# eib-32-intan-hs.net
KiCad netlist of a schematic drawn in EAGLE
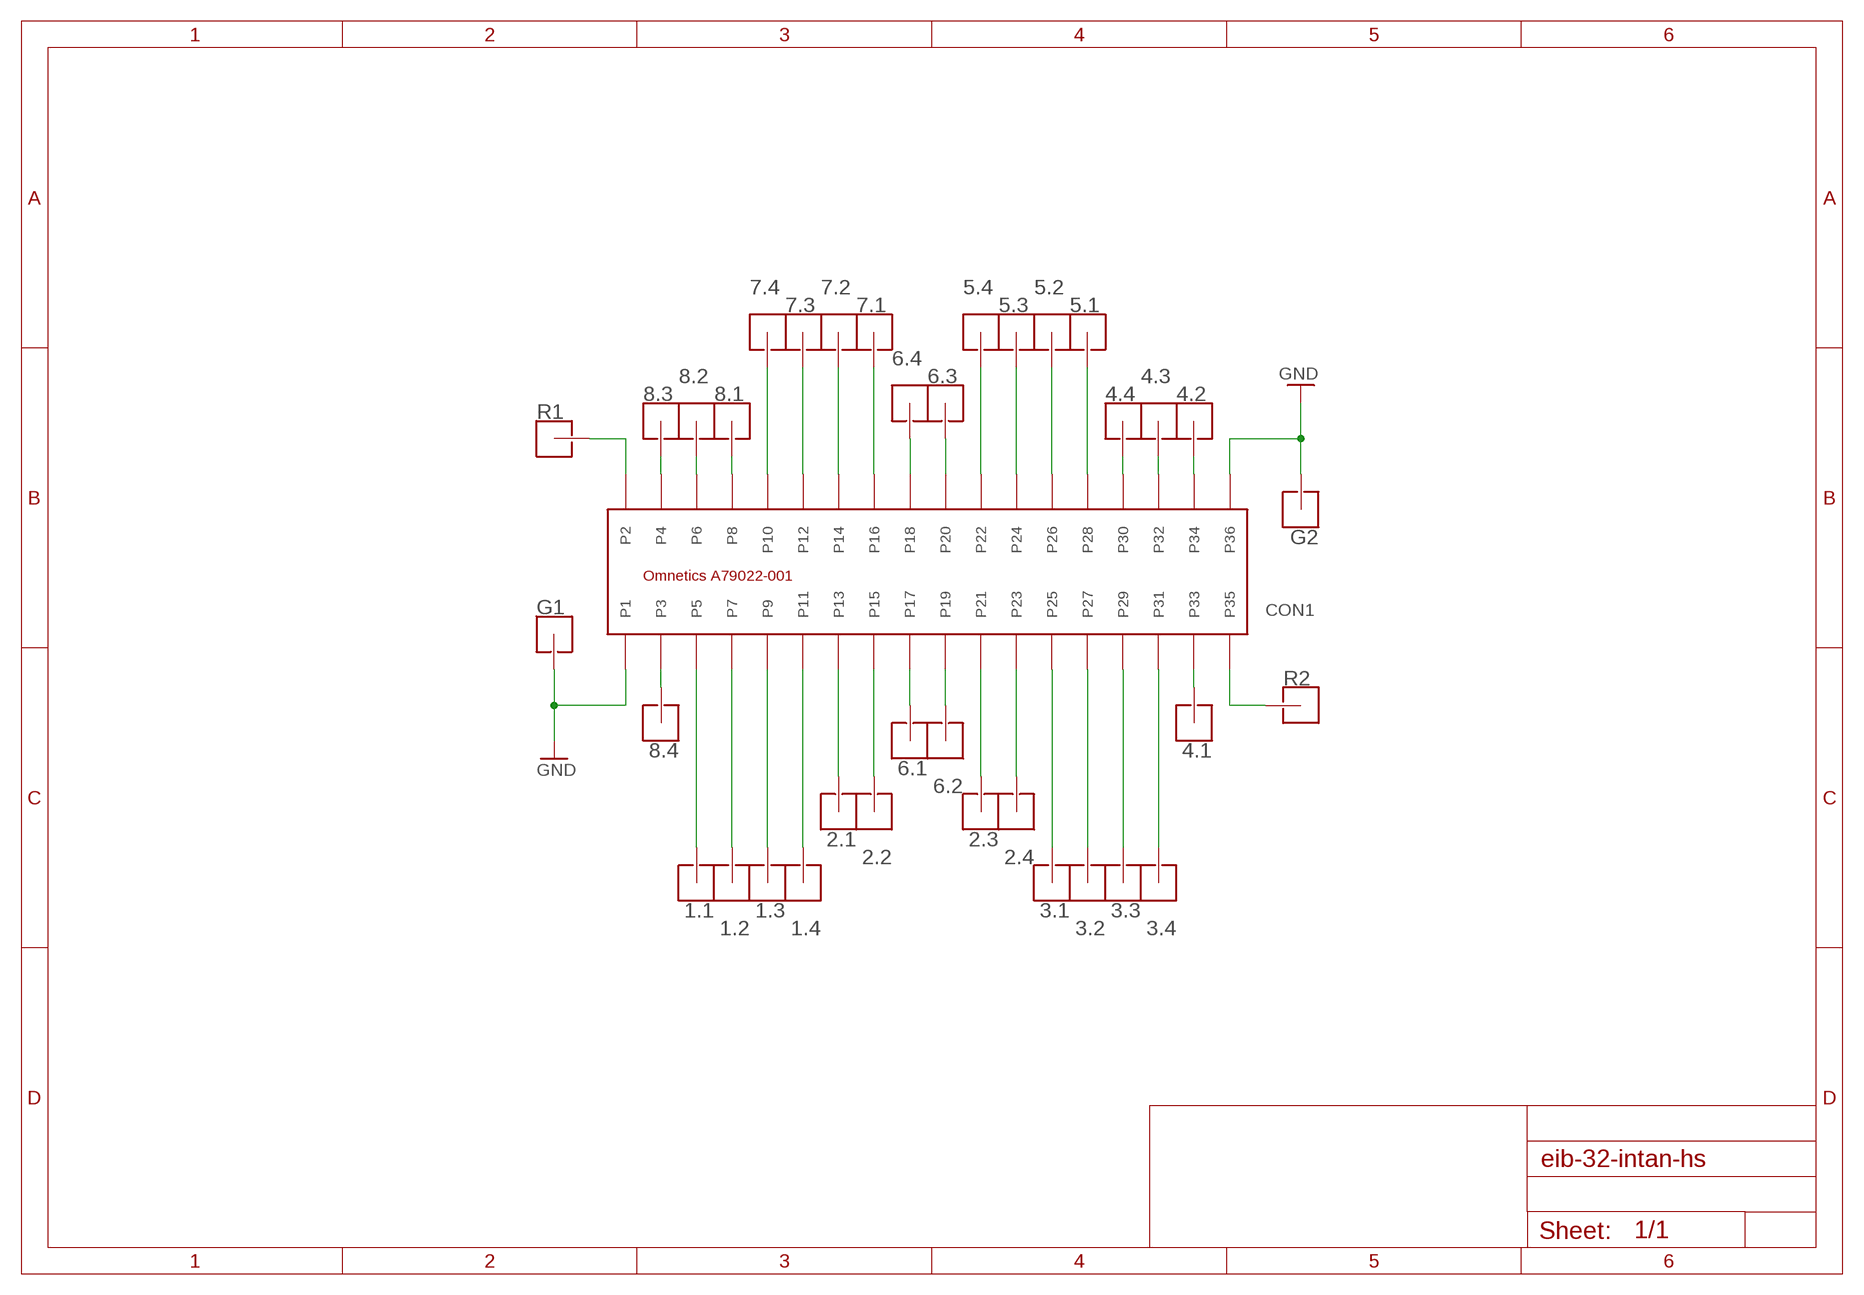
[diagram p0: schematic, sheet 1]

(export (version "E")
  (design (tool "Eeschema 10.0.6"))
  (components
    (comp (ref "1.1")
      (value "HOLE_L_G_PIN_V7")
      (footprint "eagle-import:LARGE_GOLD_PIN_V7")
      (libsource (lib "eagle-import") (part "HOLE_L_G_PIN_V7"))
    )
    (comp (ref "1.2")
      (value "HOLE_L_G_PIN_V7")
      (footprint "eagle-import:LARGE_GOLD_PIN_V7")
      (libsource (lib "eagle-import") (part "HOLE_L_G_PIN_V7"))
    )
    (comp (ref "1.3")
      (value "HOLE_L_G_PIN_V7")
      (footprint "eagle-import:LARGE_GOLD_PIN_V7")
      (libsource (lib "eagle-import") (part "HOLE_L_G_PIN_V7"))
    )
    (comp (ref "1.4")
      (value "HOLE_L_G_PIN_V7")
      (footprint "eagle-import:LARGE_GOLD_PIN_V7")
      (libsource (lib "eagle-import") (part "HOLE_L_G_PIN_V7"))
    )
    (comp (ref "2.1")
      (value "HOLE_L_G_PIN_V7")
      (footprint "eagle-import:LARGE_GOLD_PIN_V7")
      (libsource (lib "eagle-import") (part "HOLE_L_G_PIN_V7"))
    )
    (comp (ref "2.2")
      (value "HOLE_L_G_PIN_V7")
      (footprint "eagle-import:LARGE_GOLD_PIN_V7")
      (libsource (lib "eagle-import") (part "HOLE_L_G_PIN_V7"))
    )
    (comp (ref "2.3")
      (value "HOLE_L_G_PIN_V7")
      (footprint "eagle-import:LARGE_GOLD_PIN_V7")
      (libsource (lib "eagle-import") (part "HOLE_L_G_PIN_V7"))
    )
    (comp (ref "2.4")
      (value "HOLE_L_G_PIN_V7")
      (footprint "eagle-import:LARGE_GOLD_PIN_V7")
      (libsource (lib "eagle-import") (part "HOLE_L_G_PIN_V7"))
    )
    (comp (ref "3.1")
      (value "HOLE_L_G_PIN_V7")
      (footprint "eagle-import:LARGE_GOLD_PIN_V7")
      (libsource (lib "eagle-import") (part "HOLE_L_G_PIN_V7"))
    )
    (comp (ref "3.2")
      (value "HOLE_L_G_PIN_V7")
      (footprint "eagle-import:LARGE_GOLD_PIN_V7")
      (libsource (lib "eagle-import") (part "HOLE_L_G_PIN_V7"))
    )
    (comp (ref "3.3")
      (value "HOLE_L_G_PIN_V7")
      (footprint "eagle-import:LARGE_GOLD_PIN_V7")
      (libsource (lib "eagle-import") (part "HOLE_L_G_PIN_V7"))
    )
    (comp (ref "3.4")
      (value "HOLE_L_G_PIN_V7")
      (footprint "eagle-import:LARGE_GOLD_PIN_V7")
      (libsource (lib "eagle-import") (part "HOLE_L_G_PIN_V7"))
    )
    (comp (ref "4.1")
      (value "HOLE_L_G_PIN_V7")
      (footprint "eagle-import:LARGE_GOLD_PIN_V7")
      (libsource (lib "eagle-import") (part "HOLE_L_G_PIN_V7"))
    )
    (comp (ref "4.2")
      (value "HOLE_L_G_PIN_V7")
      (footprint "eagle-import:LARGE_GOLD_PIN_V7")
      (libsource (lib "eagle-import") (part "HOLE_L_G_PIN_V7"))
    )
    (comp (ref "4.3")
      (value "HOLE_L_G_PIN_V7")
      (footprint "eagle-import:LARGE_GOLD_PIN_V7")
      (libsource (lib "eagle-import") (part "HOLE_L_G_PIN_V7"))
    )
    (comp (ref "4.4")
      (value "HOLE_L_G_PIN_V7")
      (footprint "eagle-import:LARGE_GOLD_PIN_V7")
      (libsource (lib "eagle-import") (part "HOLE_L_G_PIN_V7"))
    )
    (comp (ref "5.1")
      (value "HOLE_L_G_PIN_V7")
      (footprint "eagle-import:LARGE_GOLD_PIN_V7")
      (libsource (lib "eagle-import") (part "HOLE_L_G_PIN_V7"))
    )
    (comp (ref "5.2")
      (value "HOLE_L_G_PIN_V7")
      (footprint "eagle-import:LARGE_GOLD_PIN_V7")
      (libsource (lib "eagle-import") (part "HOLE_L_G_PIN_V7"))
    )
    (comp (ref "5.3")
      (value "HOLE_L_G_PIN_V7")
      (footprint "eagle-import:LARGE_GOLD_PIN_V7")
      (libsource (lib "eagle-import") (part "HOLE_L_G_PIN_V7"))
    )
    (comp (ref "5.4")
      (value "HOLE_L_G_PIN_V7")
      (footprint "eagle-import:LARGE_GOLD_PIN_V7")
      (libsource (lib "eagle-import") (part "HOLE_L_G_PIN_V7"))
    )
    (comp (ref "6.1")
      (value "HOLE_L_G_PIN_V7")
      (footprint "eagle-import:LARGE_GOLD_PIN_V7")
      (libsource (lib "eagle-import") (part "HOLE_L_G_PIN_V7"))
    )
    (comp (ref "6.2")
      (value "HOLE_L_G_PIN_V7")
      (footprint "eagle-import:LARGE_GOLD_PIN_V7")
      (libsource (lib "eagle-import") (part "HOLE_L_G_PIN_V7"))
    )
    (comp (ref "6.3")
      (value "HOLE_L_G_PIN_V7")
      (footprint "eagle-import:LARGE_GOLD_PIN_V7")
      (libsource (lib "eagle-import") (part "HOLE_L_G_PIN_V7"))
    )
    (comp (ref "6.4")
      (value "HOLE_L_G_PIN_V7")
      (footprint "eagle-import:LARGE_GOLD_PIN_V7")
      (libsource (lib "eagle-import") (part "HOLE_L_G_PIN_V7"))
    )
    (comp (ref "7.1")
      (value "HOLE_L_G_PIN_V7")
      (footprint "eagle-import:LARGE_GOLD_PIN_V7")
      (libsource (lib "eagle-import") (part "HOLE_L_G_PIN_V7"))
    )
    (comp (ref "7.2")
      (value "HOLE_L_G_PIN_V7")
      (footprint "eagle-import:LARGE_GOLD_PIN_V7")
      (libsource (lib "eagle-import") (part "HOLE_L_G_PIN_V7"))
    )
    (comp (ref "7.3")
      (value "HOLE_L_G_PIN_V7")
      (footprint "eagle-import:LARGE_GOLD_PIN_V7")
      (libsource (lib "eagle-import") (part "HOLE_L_G_PIN_V7"))
    )
    (comp (ref "7.4")
      (value "HOLE_L_G_PIN_V7")
      (footprint "eagle-import:LARGE_GOLD_PIN_V7")
      (libsource (lib "eagle-import") (part "HOLE_L_G_PIN_V7"))
    )
    (comp (ref "8.1")
      (value "HOLE_L_G_PIN_V7")
      (footprint "eagle-import:LARGE_GOLD_PIN_V7")
      (libsource (lib "eagle-import") (part "HOLE_L_G_PIN_V7"))
    )
    (comp (ref "8.2")
      (value "HOLE_L_G_PIN_V7")
      (footprint "eagle-import:LARGE_GOLD_PIN_V7")
      (libsource (lib "eagle-import") (part "HOLE_L_G_PIN_V7"))
    )
    (comp (ref "8.3")
      (value "HOLE_L_G_PIN_V7")
      (footprint "eagle-import:LARGE_GOLD_PIN_V7")
      (libsource (lib "eagle-import") (part "HOLE_L_G_PIN_V7"))
    )
    (comp (ref "8.4")
      (value "HOLE_L_G_PIN_V7")
      (footprint "eagle-import:LARGE_GOLD_PIN_V7")
      (libsource (lib "eagle-import") (part "HOLE_L_G_PIN_V7"))
    )
    (comp (ref "CON1")
      (value "A79022-001_MALESMD")
      (footprint "eagle-import:A79026-001_MALE")
      (libsource (lib "eagle-import") (part "A79022-001_MALESMD"))
    )
    (comp (ref "G1")
      (value "HOLE_L_G_PIN_V7")
      (footprint "eagle-import:LARGE_GOLD_PIN_V7")
      (libsource (lib "eagle-import") (part "HOLE_L_G_PIN_V7"))
    )
    (comp (ref "G2")
      (value "HOLE_L_G_PIN_V7")
      (footprint "eagle-import:LARGE_GOLD_PIN_V7")
      (libsource (lib "eagle-import") (part "HOLE_L_G_PIN_V7"))
    )
    (comp (ref "R1")
      (value "HOLE_L_G_PIN_V7")
      (footprint "eagle-import:LARGE_GOLD_PIN_V7")
      (libsource (lib "eagle-import") (part "HOLE_L_G_PIN_V7"))
    )
    (comp (ref "R2")
      (value "HOLE_L_G_PIN_V7")
      (footprint "eagle-import:LARGE_GOLD_PIN_V7")
      (libsource (lib "eagle-import") (part "HOLE_L_G_PIN_V7"))
    )
  )
  (nets
    (net (code "1") (name "GND") (class "Default")
      (node (ref "CON1") (pin "P1") (pinfunction "P1_P1") (pintype "bidirectional"))
      (node (ref "CON1") (pin "P36") (pinfunction "P36_P36") (pintype "bidirectional"))
      (node (ref "G1") (pin "P$1") (pinfunction "P$1_P$1") (pintype "bidirectional"))
      (node (ref "G2") (pin "P$1") (pinfunction "P$1_P$1") (pintype "bidirectional"))
    )
    (net (code "2") (name "Net-(1.1-PadP$1)") (class "Default")
      (node (ref "1.1") (pin "P$1") (pinfunction "P$1_P$1") (pintype "bidirectional"))
      (node (ref "CON1") (pin "P5") (pinfunction "P5_P5") (pintype "bidirectional"))
    )
    (net (code "3") (name "Net-(1.2-PadP$1)") (class "Default")
      (node (ref "1.2") (pin "P$1") (pinfunction "P$1_P$1") (pintype "bidirectional"))
      (node (ref "CON1") (pin "P7") (pinfunction "P7_P7") (pintype "bidirectional"))
    )
    (net (code "4") (name "Net-(1.3-PadP$1)") (class "Default")
      (node (ref "1.3") (pin "P$1") (pinfunction "P$1_P$1") (pintype "bidirectional"))
      (node (ref "CON1") (pin "P9") (pinfunction "P9_P9") (pintype "bidirectional"))
    )
    (net (code "5") (name "Net-(1.4-PadP$1)") (class "Default")
      (node (ref "1.4") (pin "P$1") (pinfunction "P$1_P$1") (pintype "bidirectional"))
      (node (ref "CON1") (pin "P11") (pinfunction "P11_P11") (pintype "bidirectional"))
    )
    (net (code "6") (name "Net-(2.1-PadP$1)") (class "Default")
      (node (ref "2.1") (pin "P$1") (pinfunction "P$1_P$1") (pintype "bidirectional"))
      (node (ref "CON1") (pin "P13") (pinfunction "P13_P13") (pintype "bidirectional"))
    )
    (net (code "7") (name "Net-(2.2-PadP$1)") (class "Default")
      (node (ref "2.2") (pin "P$1") (pinfunction "P$1_P$1") (pintype "bidirectional"))
      (node (ref "CON1") (pin "P15") (pinfunction "P15_P15") (pintype "bidirectional"))
    )
    (net (code "8") (name "Net-(2.3-PadP$1)") (class "Default")
      (node (ref "2.3") (pin "P$1") (pinfunction "P$1_P$1") (pintype "bidirectional"))
      (node (ref "CON1") (pin "P21") (pinfunction "P21_P21") (pintype "bidirectional"))
    )
    (net (code "9") (name "Net-(2.4-PadP$1)") (class "Default")
      (node (ref "2.4") (pin "P$1") (pinfunction "P$1_P$1") (pintype "bidirectional"))
      (node (ref "CON1") (pin "P23") (pinfunction "P23_P23") (pintype "bidirectional"))
    )
    (net (code "10") (name "Net-(3.1-PadP$1)") (class "Default")
      (node (ref "3.1") (pin "P$1") (pinfunction "P$1_P$1") (pintype "bidirectional"))
      (node (ref "CON1") (pin "P25") (pinfunction "P25_P25") (pintype "bidirectional"))
    )
    (net (code "11") (name "Net-(3.2-PadP$1)") (class "Default")
      (node (ref "3.2") (pin "P$1") (pinfunction "P$1_P$1") (pintype "bidirectional"))
      (node (ref "CON1") (pin "P27") (pinfunction "P27_P27") (pintype "bidirectional"))
    )
    (net (code "12") (name "Net-(3.3-PadP$1)") (class "Default")
      (node (ref "3.3") (pin "P$1") (pinfunction "P$1_P$1") (pintype "bidirectional"))
      (node (ref "CON1") (pin "P29") (pinfunction "P29_P29") (pintype "bidirectional"))
    )
    (net (code "13") (name "Net-(3.4-PadP$1)") (class "Default")
      (node (ref "3.4") (pin "P$1") (pinfunction "P$1_P$1") (pintype "bidirectional"))
      (node (ref "CON1") (pin "P31") (pinfunction "P31_P31") (pintype "bidirectional"))
    )
    (net (code "14") (name "Net-(4.1-PadP$1)") (class "Default")
      (node (ref "4.1") (pin "P$1") (pinfunction "P$1_P$1") (pintype "bidirectional"))
      (node (ref "CON1") (pin "P33") (pinfunction "P33_P33") (pintype "bidirectional"))
    )
    (net (code "15") (name "Net-(4.2-PadP$1)") (class "Default")
      (node (ref "4.2") (pin "P$1") (pinfunction "P$1_P$1") (pintype "bidirectional"))
      (node (ref "CON1") (pin "P34") (pinfunction "P34_P34") (pintype "bidirectional"))
    )
    (net (code "16") (name "Net-(4.3-PadP$1)") (class "Default")
      (node (ref "4.3") (pin "P$1") (pinfunction "P$1_P$1") (pintype "bidirectional"))
      (node (ref "CON1") (pin "P32") (pinfunction "P32_P32") (pintype "bidirectional"))
    )
    (net (code "17") (name "Net-(4.4-PadP$1)") (class "Default")
      (node (ref "4.4") (pin "P$1") (pinfunction "P$1_P$1") (pintype "bidirectional"))
      (node (ref "CON1") (pin "P30") (pinfunction "P30_P30") (pintype "bidirectional"))
    )
    (net (code "18") (name "Net-(5.1-PadP$1)") (class "Default")
      (node (ref "5.1") (pin "P$1") (pinfunction "P$1_P$1") (pintype "bidirectional"))
      (node (ref "CON1") (pin "P28") (pinfunction "P28_P28") (pintype "bidirectional"))
    )
    (net (code "19") (name "Net-(5.2-PadP$1)") (class "Default")
      (node (ref "5.2") (pin "P$1") (pinfunction "P$1_P$1") (pintype "bidirectional"))
      (node (ref "CON1") (pin "P26") (pinfunction "P26_P26") (pintype "bidirectional"))
    )
    (net (code "20") (name "Net-(5.3-PadP$1)") (class "Default")
      (node (ref "5.3") (pin "P$1") (pinfunction "P$1_P$1") (pintype "bidirectional"))
      (node (ref "CON1") (pin "P24") (pinfunction "P24_P24") (pintype "bidirectional"))
    )
    (net (code "21") (name "Net-(5.4-PadP$1)") (class "Default")
      (node (ref "5.4") (pin "P$1") (pinfunction "P$1_P$1") (pintype "bidirectional"))
      (node (ref "CON1") (pin "P22") (pinfunction "P22_P22") (pintype "bidirectional"))
    )
    (net (code "22") (name "Net-(6.1-PadP$1)") (class "Default")
      (node (ref "6.1") (pin "P$1") (pinfunction "P$1_P$1") (pintype "bidirectional"))
      (node (ref "CON1") (pin "P17") (pinfunction "P17_P17") (pintype "bidirectional"))
    )
    (net (code "23") (name "Net-(6.2-PadP$1)") (class "Default")
      (node (ref "6.2") (pin "P$1") (pinfunction "P$1_P$1") (pintype "bidirectional"))
      (node (ref "CON1") (pin "P19") (pinfunction "P19_P19") (pintype "bidirectional"))
    )
    (net (code "24") (name "Net-(6.3-PadP$1)") (class "Default")
      (node (ref "6.3") (pin "P$1") (pinfunction "P$1_P$1") (pintype "bidirectional"))
      (node (ref "CON1") (pin "P20") (pinfunction "P20_P20") (pintype "bidirectional"))
    )
    (net (code "25") (name "Net-(6.4-PadP$1)") (class "Default")
      (node (ref "6.4") (pin "P$1") (pinfunction "P$1_P$1") (pintype "bidirectional"))
      (node (ref "CON1") (pin "P18") (pinfunction "P18_P18") (pintype "bidirectional"))
    )
    (net (code "26") (name "Net-(7.1-PadP$1)") (class "Default")
      (node (ref "7.1") (pin "P$1") (pinfunction "P$1_P$1") (pintype "bidirectional"))
      (node (ref "CON1") (pin "P16") (pinfunction "P16_P16") (pintype "bidirectional"))
    )
    (net (code "27") (name "Net-(7.2-PadP$1)") (class "Default")
      (node (ref "7.2") (pin "P$1") (pinfunction "P$1_P$1") (pintype "bidirectional"))
      (node (ref "CON1") (pin "P14") (pinfunction "P14_P14") (pintype "bidirectional"))
    )
    (net (code "28") (name "Net-(7.3-PadP$1)") (class "Default")
      (node (ref "7.3") (pin "P$1") (pinfunction "P$1_P$1") (pintype "bidirectional"))
      (node (ref "CON1") (pin "P12") (pinfunction "P12_P12") (pintype "bidirectional"))
    )
    (net (code "29") (name "Net-(7.4-PadP$1)") (class "Default")
      (node (ref "7.4") (pin "P$1") (pinfunction "P$1_P$1") (pintype "bidirectional"))
      (node (ref "CON1") (pin "P10") (pinfunction "P10_P10") (pintype "bidirectional"))
    )
    (net (code "30") (name "Net-(8.1-PadP$1)") (class "Default")
      (node (ref "8.1") (pin "P$1") (pinfunction "P$1_P$1") (pintype "bidirectional"))
      (node (ref "CON1") (pin "P8") (pinfunction "P8_P8") (pintype "bidirectional"))
    )
    (net (code "31") (name "Net-(8.2-PadP$1)") (class "Default")
      (node (ref "8.2") (pin "P$1") (pinfunction "P$1_P$1") (pintype "bidirectional"))
      (node (ref "CON1") (pin "P6") (pinfunction "P6_P6") (pintype "bidirectional"))
    )
    (net (code "32") (name "Net-(8.3-PadP$1)") (class "Default")
      (node (ref "8.3") (pin "P$1") (pinfunction "P$1_P$1") (pintype "bidirectional"))
      (node (ref "CON1") (pin "P4") (pinfunction "P4_P4") (pintype "bidirectional"))
    )
    (net (code "33") (name "Net-(8.4-PadP$1)") (class "Default")
      (node (ref "8.4") (pin "P$1") (pinfunction "P$1_P$1") (pintype "bidirectional"))
      (node (ref "CON1") (pin "P3") (pinfunction "P3_P3") (pintype "bidirectional"))
    )
    (net (code "34") (name "Net-(CON1-PadP2)") (class "Default")
      (node (ref "CON1") (pin "P2") (pinfunction "P2_P2") (pintype "bidirectional"))
      (node (ref "R1") (pin "P$1") (pinfunction "P$1_P$1") (pintype "bidirectional"))
    )
    (net (code "35") (name "Net-(CON1-PadP35)") (class "Default")
      (node (ref "CON1") (pin "P35") (pinfunction "P35_P35") (pintype "bidirectional"))
      (node (ref "R2") (pin "P$1") (pinfunction "P$1_P$1") (pintype "bidirectional"))
    )
  )
)
